# BTP_Halleffectsensor.net
KiCad netlist of a schematic drawn in EAGLE
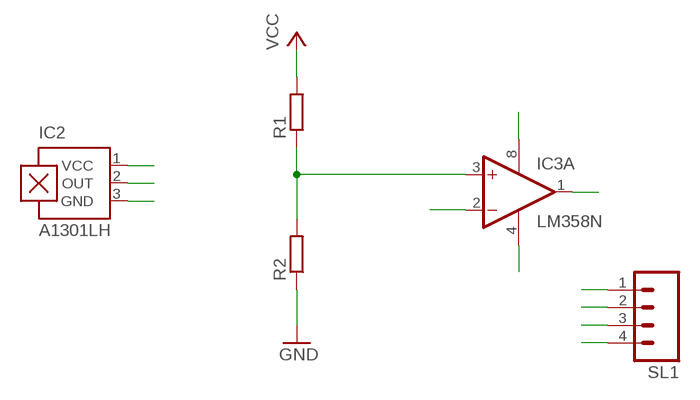
[diagram p0: schematic, sheet 1]

(export (version "E")
  (design (tool "Eeschema 10.0.6"))
  (components
    (comp (ref "IC2")
      (value "A1301LH")
      (footprint "eagle-import:SOT23-W")
      (fields (field (name "MF") "ALLEGRO MICROSYSTEMS, INC.") (field (name "MPN") "A1301ELHLT-T"))
      (libsource (lib "eagle-import") (part "A13?LH01"))
    )
    (comp (ref "IC3")
      (value "LM358N")
      (footprint "eagle-import:DIL08")
      (libsource (lib "eagle-import") (part "LM358N"))
    )
    (comp (ref "R1")
      (value "R-EU_0204/7")
      (footprint "eagle-import:0204_7")
      (libsource (lib "eagle-import") (part "R-EU_0204/7"))
    )
    (comp (ref "R2")
      (value "R-EU_0204/7")
      (footprint "eagle-import:0204_7")
      (libsource (lib "eagle-import") (part "R-EU_0204/7"))
    )
    (comp (ref "SL1")
      (value "M04")
      (footprint "eagle-import:04P")
      (libsource (lib "eagle-import") (part "M04"))
    )
  )
  (nets
    (net (code "1") (name "/DOUT") (class "Default")
      (node (ref "IC3") (pin "1") (pinfunction "OUT_1") (pintype "output"))
      (node (ref "SL1") (pin "4") (pinfunction "4_4") (pintype "passive"))
    )
    (net (code "2") (name "/OUT") (class "Default")
      (node (ref "IC2") (pin "2") (pinfunction "OUT_2") (pintype "output"))
      (node (ref "IC3") (pin "2") (pinfunction "-IN_2") (pintype "input"))
      (node (ref "SL1") (pin "2") (pinfunction "2_2") (pintype "passive"))
    )
    (net (code "3") (name "GND") (class "Default")
      (node (ref "IC2") (pin "3") (pinfunction "GND_3") (pintype "power_in"))
      (node (ref "IC3") (pin "4") (pinfunction "V-_4") (pintype "power_in"))
      (node (ref "R2") (pin "1") (pinfunction "1_1") (pintype "passive"))
      (node (ref "SL1") (pin "1") (pinfunction "1_1") (pintype "passive"))
    )
    (net (code "4") (name "Net-(IC3A-+IN)") (class "Default")
      (node (ref "IC3") (pin "3") (pinfunction "+IN_3") (pintype "input"))
      (node (ref "R1") (pin "1") (pinfunction "1_1") (pintype "passive"))
      (node (ref "R2") (pin "2") (pinfunction "2_2") (pintype "passive"))
    )
    (net (code "5") (name "VCC") (class "Default")
      (node (ref "IC2") (pin "1") (pinfunction "VCC_1") (pintype "power_in"))
      (node (ref "IC3") (pin "8") (pinfunction "V+_8") (pintype "power_in"))
      (node (ref "R1") (pin "2") (pinfunction "2_2") (pintype "passive"))
      (node (ref "SL1") (pin "3") (pinfunction "3_3") (pintype "passive"))
    )
  )
)
